# GLCD_Board.net
KiCad netlist of a schematic drawn in Altium Designer
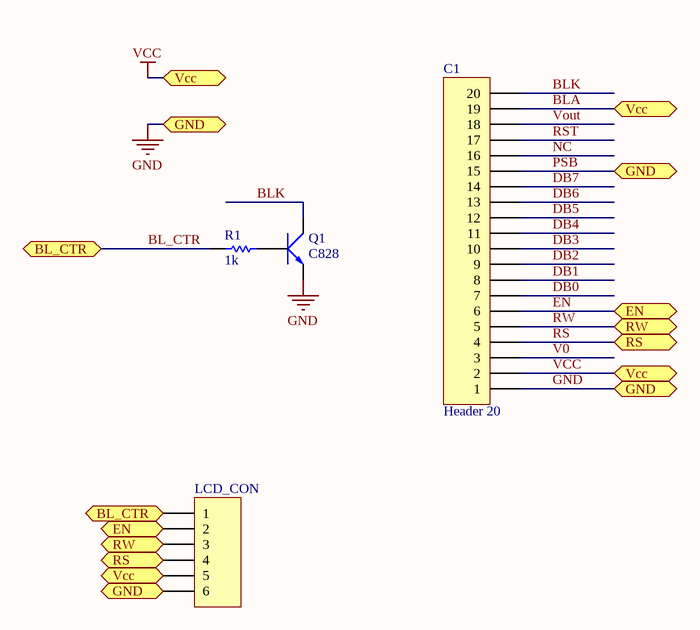
[diagram p0: GLCD_Board.SchDoc]

(export (version "E")
  (design (tool "Eeschema 10.0.6"))
  (components
    (comp (ref "C1")
      (value "Header 20")
      (footprint "HDR1X20")
      (description "Header, 20-Pin")
      (fields (field (name "PUBLISHER") "Altium Limited"))
      (libsource (lib "Miscellaneous Connectors") (part "Header 20"))
    )
    (comp (ref "LCD_CON")
      (value "Header 6")
      (footprint "Header 6 way 90")
      (description "Header, 6-Pin")
      (fields (field (name "PUBLISHER") "Altium Limited"))
      (libsource (lib "Miscellaneous Connectors") (part "Header 6"))
    )
    (comp (ref "Q1")
      (value "C828")
      (footprint "SOT23 TOP")
      (description "Transistor C828 C1815....")
      (libsource (lib "Tuan") (part "NPN"))
    )
    (comp (ref "R1")
      (value "1k")
      (footprint "RESC1608N_ZERO")
      (fields (field (name "Comment") "Res"))
      (libsource (lib "Tuan") (part "Res"))
    )
  )
  (nets
    (net (code "1") (name "/BLK") (class "Default")
      (node (ref "C1") (pin "20") (pinfunction "20_20") (pintype "passive"))
      (node (ref "Q1") (pin "2") (pinfunction "C_2") (pintype "passive"))
    )
    (net (code "2") (name "/BL_CTR") (class "Default")
      (node (ref "LCD_CON") (pin "1") (pinfunction "1_1") (pintype "passive"))
      (node (ref "R1") (pin "1") (pinfunction "1_1") (pintype "passive"))
    )
    (net (code "3") (name "/DB0") (class "Default")
      (node (ref "C1") (pin "7") (pinfunction "7_7") (pintype "passive"))
    )
    (net (code "4") (name "/DB1") (class "Default")
      (node (ref "C1") (pin "8") (pinfunction "8_8") (pintype "passive"))
    )
    (net (code "5") (name "/DB2") (class "Default")
      (node (ref "C1") (pin "9") (pinfunction "9_9") (pintype "passive"))
    )
    (net (code "6") (name "/DB3") (class "Default")
      (node (ref "C1") (pin "10") (pinfunction "10_10") (pintype "passive"))
    )
    (net (code "7") (name "/DB4") (class "Default")
      (node (ref "C1") (pin "11") (pinfunction "11_11") (pintype "passive"))
    )
    (net (code "8") (name "/DB5") (class "Default")
      (node (ref "C1") (pin "12") (pinfunction "12_12") (pintype "passive"))
    )
    (net (code "9") (name "/DB6") (class "Default")
      (node (ref "C1") (pin "13") (pinfunction "13_13") (pintype "passive"))
    )
    (net (code "10") (name "/DB7") (class "Default")
      (node (ref "C1") (pin "14") (pinfunction "14_14") (pintype "passive"))
    )
    (net (code "11") (name "/EN") (class "Default")
      (node (ref "C1") (pin "6") (pinfunction "6_6") (pintype "passive"))
      (node (ref "LCD_CON") (pin "2") (pinfunction "2_2") (pintype "passive"))
    )
    (net (code "12") (name "/NC") (class "Default")
      (node (ref "C1") (pin "16") (pinfunction "16_16") (pintype "passive"))
    )
    (net (code "13") (name "/RS") (class "Default")
      (node (ref "C1") (pin "4") (pinfunction "4_4") (pintype "passive"))
      (node (ref "LCD_CON") (pin "4") (pinfunction "4_4") (pintype "passive"))
    )
    (net (code "14") (name "/RST") (class "Default")
      (node (ref "C1") (pin "17") (pinfunction "17_17") (pintype "passive"))
    )
    (net (code "15") (name "/RW") (class "Default")
      (node (ref "C1") (pin "5") (pinfunction "5_5") (pintype "passive"))
      (node (ref "LCD_CON") (pin "3") (pinfunction "3_3") (pintype "passive"))
    )
    (net (code "16") (name "/V0") (class "Default")
      (node (ref "C1") (pin "3") (pinfunction "3_3") (pintype "passive"))
    )
    (net (code "17") (name "/Vout") (class "Default")
      (node (ref "C1") (pin "18") (pinfunction "18_18") (pintype "passive"))
    )
    (net (code "18") (name "GND") (class "Default")
      (node (ref "C1") (pin "1") (pinfunction "1_1") (pintype "passive"))
      (node (ref "C1") (pin "15") (pinfunction "15_15") (pintype "passive"))
      (node (ref "LCD_CON") (pin "6") (pinfunction "6_6") (pintype "passive"))
      (node (ref "Q1") (pin "3") (pinfunction "E_3") (pintype "passive"))
    )
    (net (code "19") (name "Net-(Q1-B)") (class "Default")
      (node (ref "Q1") (pin "1") (pinfunction "B_1") (pintype "passive"))
      (node (ref "R1") (pin "2") (pinfunction "2_2") (pintype "passive"))
    )
    (net (code "20") (name "VCC") (class "Default")
      (node (ref "C1") (pin "19") (pinfunction "19_19") (pintype "passive"))
      (node (ref "C1") (pin "2") (pinfunction "2_2") (pintype "passive"))
      (node (ref "LCD_CON") (pin "5") (pinfunction "5_5") (pintype "passive"))
    )
  )
)
